# Complete_ePaper_Shoe_Board.net
KiCad netlist of a schematic drawn in EAGLE
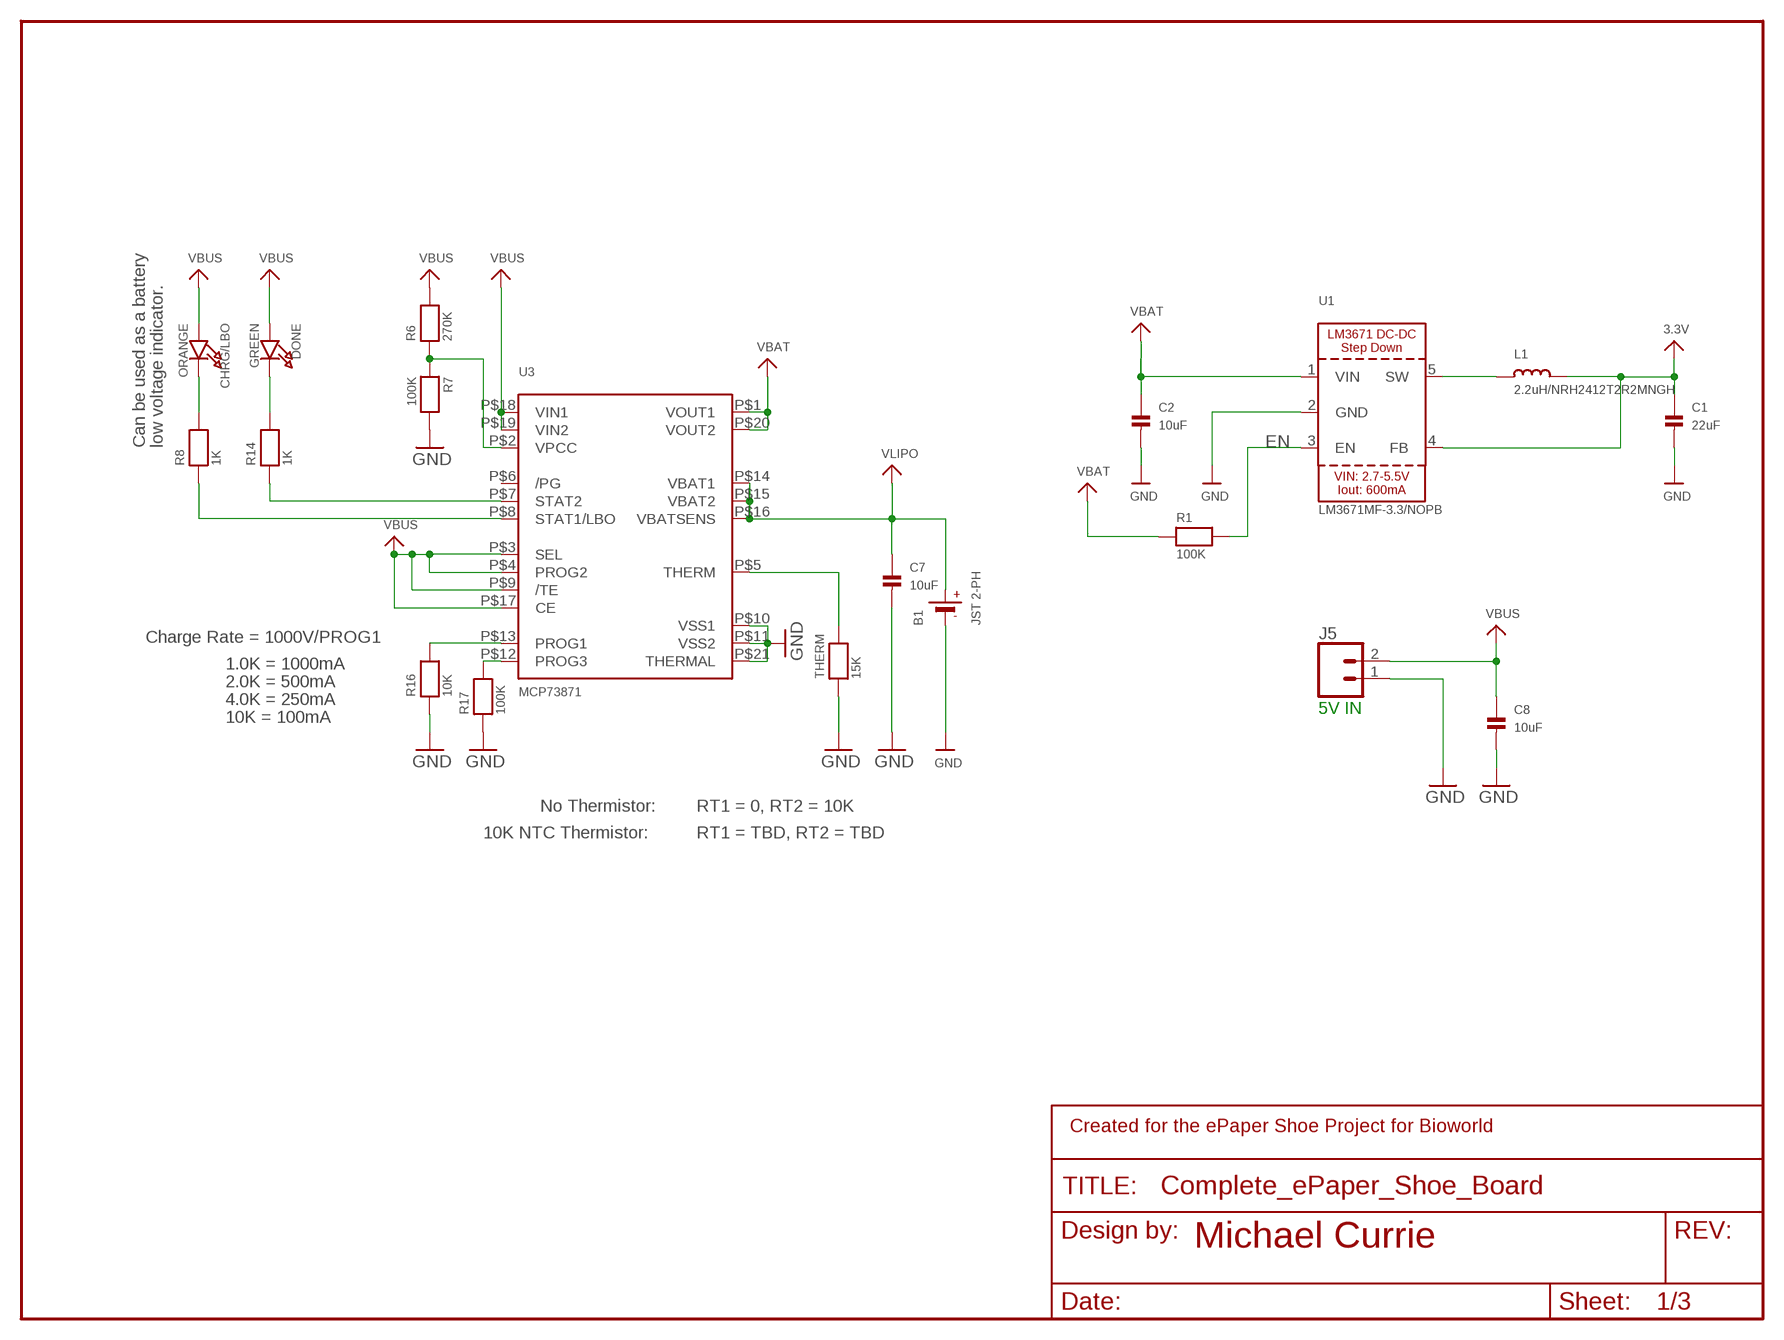
[diagram p0: schematic, sheet 1]
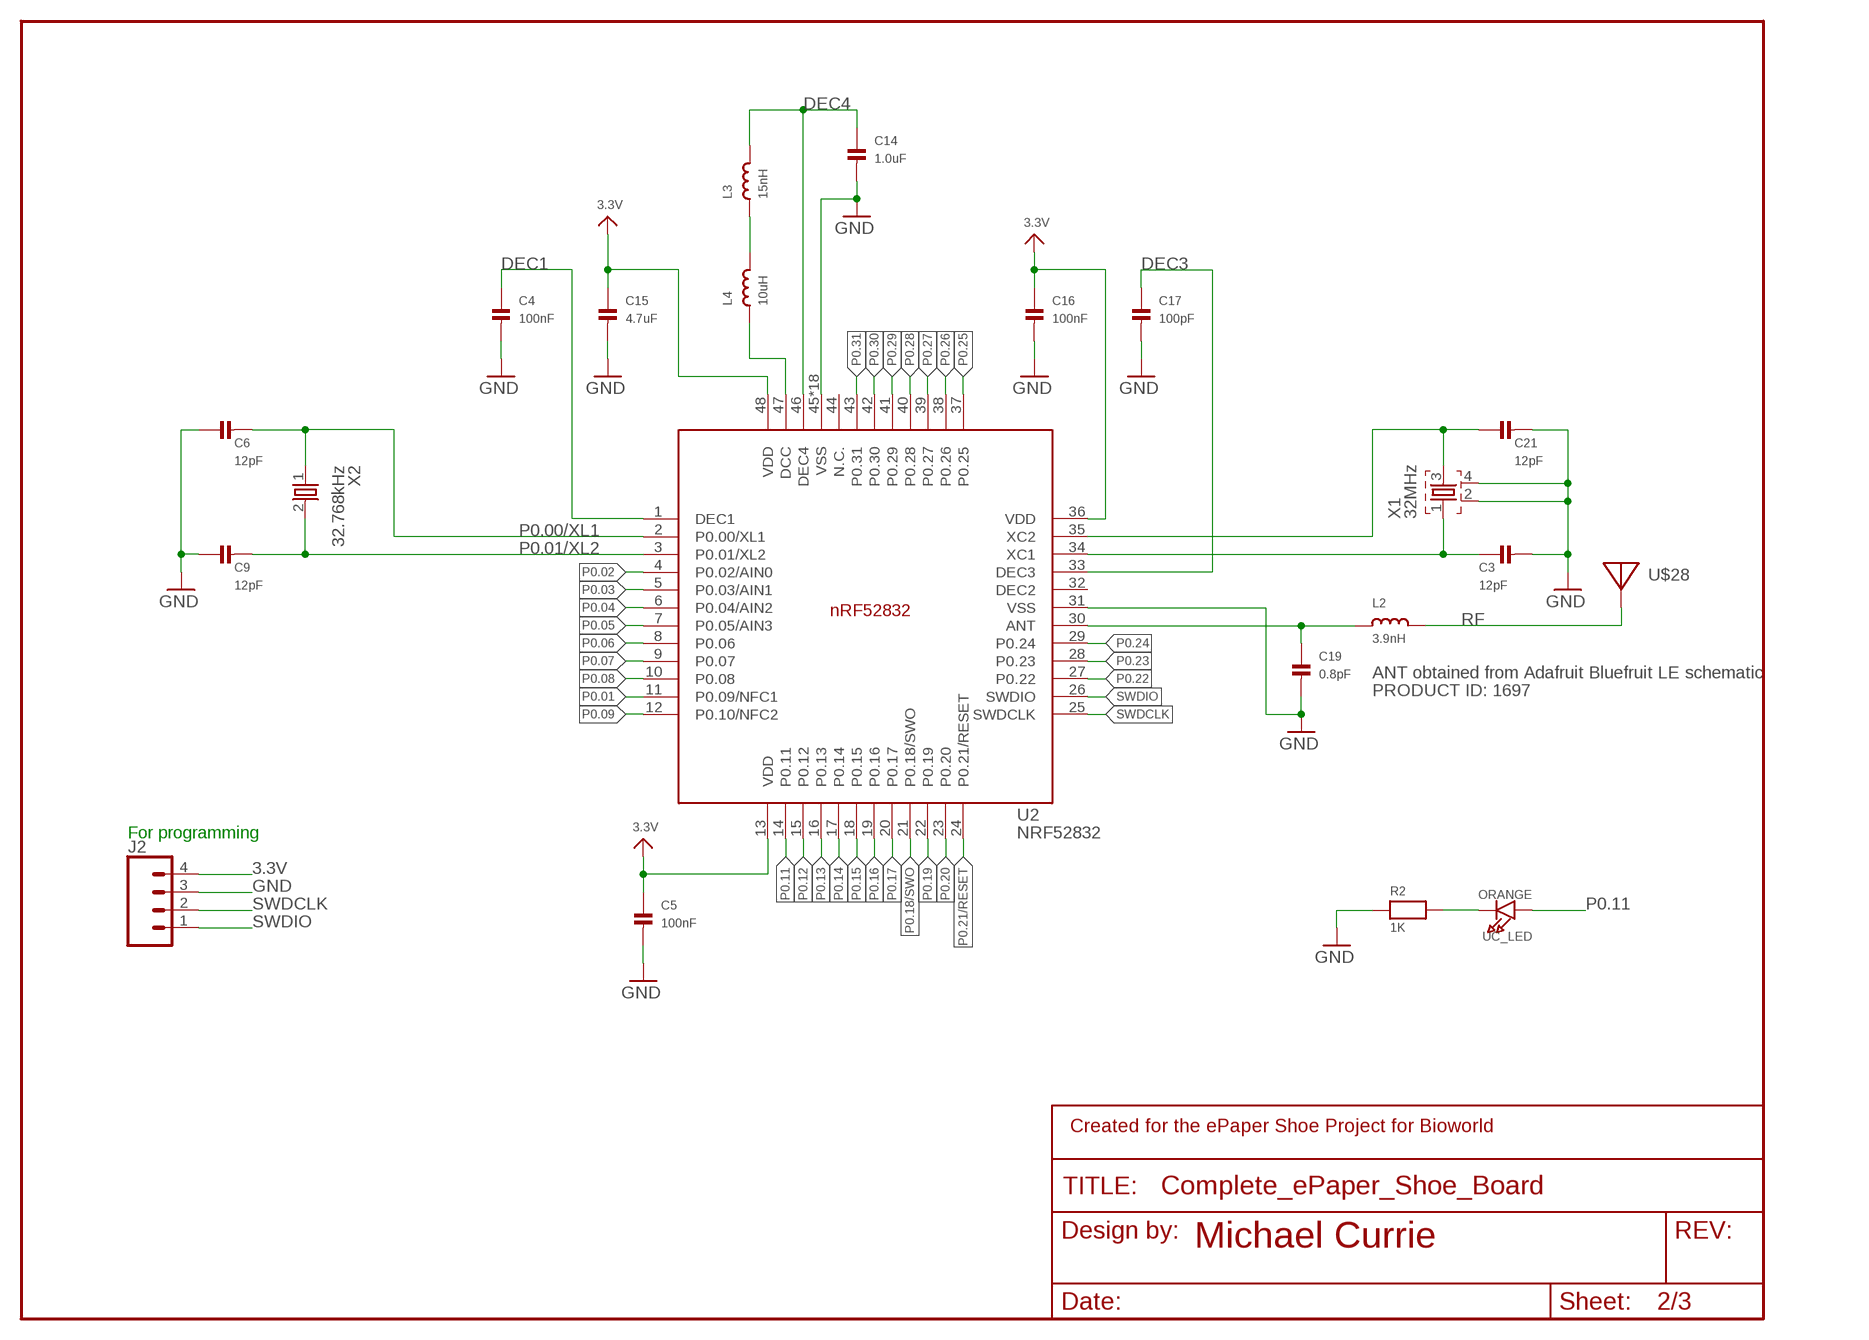
[diagram p1: schematic, sheet 2]
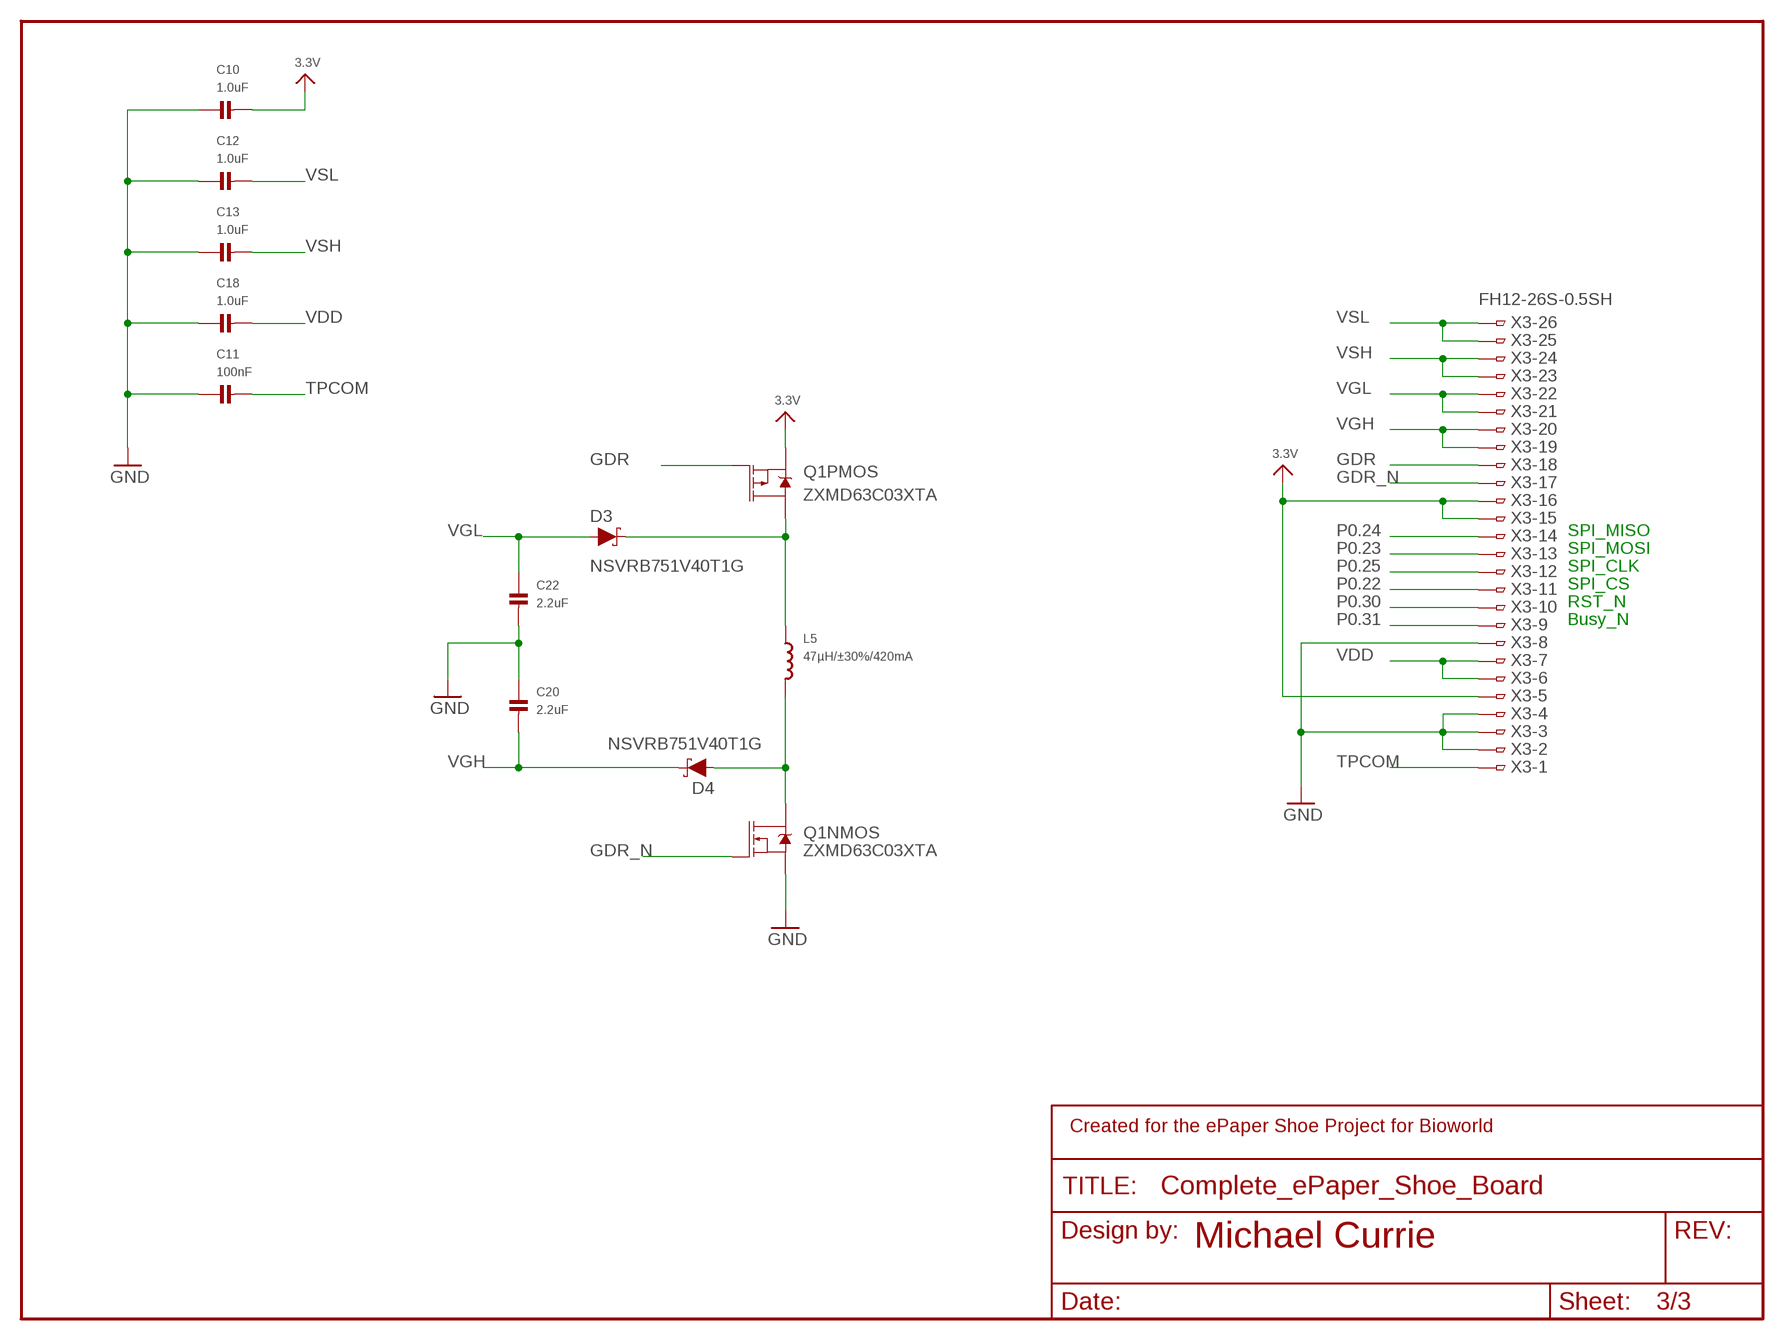
[diagram p2: schematic, sheet 3]

(export (version "E")
  (design (tool "Eeschema 10.0.6"))
  (components
    (comp (ref "C3")
      (value "12pF")
      (footprint "eagle-import:0805")
      (libsource (lib "eagle-import") (part "CAP_CERAMIC0805"))
    )
    (comp (ref "C4")
      (value "100nF")
      (footprint "eagle-import:0805")
      (libsource (lib "eagle-import") (part "CAP_CERAMIC0805"))
    )
    (comp (ref "C5")
      (value "100nF")
      (footprint "eagle-import:0805")
      (libsource (lib "eagle-import") (part "CAP_CERAMIC0805"))
    )
    (comp (ref "C6")
      (value "12pF")
      (footprint "eagle-import:0805")
      (libsource (lib "eagle-import") (part "CAP_CERAMIC0805"))
    )
    (comp (ref "C9")
      (value "12pF")
      (footprint "eagle-import:0805")
      (libsource (lib "eagle-import") (part "CAP_CERAMIC0805"))
    )
    (comp (ref "C14")
      (value "1.0uF")
      (footprint "eagle-import:0805")
      (libsource (lib "eagle-import") (part "CAP_CERAMIC0805"))
    )
    (comp (ref "C15")
      (value "4.7uF")
      (footprint "eagle-import:0805")
      (libsource (lib "eagle-import") (part "CAP_CERAMIC0805"))
    )
    (comp (ref "C16")
      (value "100nF")
      (footprint "eagle-import:0805")
      (libsource (lib "eagle-import") (part "CAP_CERAMIC0805"))
    )
    (comp (ref "C17")
      (value "100pF")
      (footprint "eagle-import:0805")
      (libsource (lib "eagle-import") (part "CAP_CERAMIC0805"))
    )
    (comp (ref "C19")
      (value "0.8pF")
      (footprint "eagle-import:0805")
      (libsource (lib "eagle-import") (part "CAP_CERAMIC0805"))
    )
    (comp (ref "C21")
      (value "12pF")
      (footprint "eagle-import:0805")
      (libsource (lib "eagle-import") (part "CAP_CERAMIC0805"))
    )
    (comp (ref "FRAME2")
      (value "FRAME-LETTER-MICHAELNO_PACKAGE")
      (footprint "eagle-import:DUMMY")
      (fields (field (name "DESIGNER") "Nobody"))
      (libsource (lib "eagle-import") (part "FRAME-LETTER-MICHAELNO_PACKAGE"))
    )
    (comp (ref "J2")
      (value "CONN_04")
      (footprint "eagle-import:1X04")
      (libsource (lib "eagle-import") (part "CONN_04"))
    )
    (comp (ref "L2")
      (value "3.9nH")
      (footprint "eagle-import:0805")
      (libsource (lib "eagle-import") (part "INDUCTOR0805"))
    )
    (comp (ref "L3")
      (value "15nH")
      (footprint "eagle-import:0805")
      (libsource (lib "eagle-import") (part "INDUCTOR0805"))
    )
    (comp (ref "L4")
      (value "10uH")
      (footprint "eagle-import:0805")
      (libsource (lib "eagle-import") (part "INDUCTOR0805"))
    )
    (comp (ref "R2")
      (value "1K")
      (footprint "eagle-import:0805")
      (libsource (lib "eagle-import") (part "RESISTOR0805"))
    )
    (comp (ref "U$28")
      (value "ANTENNA_PCBNRF8001_1.6MM")
      (footprint "eagle-import:ANT_PCB_2.4GHZ_NRF8001_1.6MM_1OZ")
      (libsource (lib "eagle-import") (part "ANTENNA_PCBNRF8001_1.6MM"))
    )
    (comp (ref "U2")
      (value "NRF52832")
      (footprint "eagle-import:QFN40P600X600X90-48_N")
      (libsource (lib "eagle-import") (part "NRF52832"))
    )
    (comp (ref "UC_LED")
      (value "ORANGE")
      (footprint "eagle-import:CHIPLED_0805_NOOUTLINE")
      (libsource (lib "eagle-import") (part "LED0805_NOOUTLINE"))
    )
    (comp (ref "X1")
      (value "32MHz")
      (footprint "eagle-import:BT-XTAL_2016_N")
      (libsource (lib "eagle-import") (part "XTAL_32MHZ"))
    )
    (comp (ref "X2")
      (value "32.768kHz")
      (footprint "eagle-import:XTAL_3215_N")
      (libsource (lib "eagle-import") (part "XTAL_32KHZ"))
    )
    (comp (ref "C10")
      (value "1.0uF")
      (footprint "eagle-import:0805")
      (libsource (lib "eagle-import") (part "CAP_CERAMIC0805"))
    )
    (comp (ref "C11")
      (value "100nF")
      (footprint "eagle-import:0805")
      (libsource (lib "eagle-import") (part "CAP_CERAMIC0805"))
    )
    (comp (ref "C12")
      (value "1.0uF")
      (footprint "eagle-import:0805")
      (libsource (lib "eagle-import") (part "CAP_CERAMIC0805"))
    )
    (comp (ref "C13")
      (value "1.0uF")
      (footprint "eagle-import:0805")
      (libsource (lib "eagle-import") (part "CAP_CERAMIC0805"))
    )
    (comp (ref "C18")
      (value "1.0uF")
      (footprint "eagle-import:0805")
      (libsource (lib "eagle-import") (part "CAP_CERAMIC0805"))
    )
    (comp (ref "C20")
      (value "2.2uF")
      (footprint "eagle-import:0805")
      (libsource (lib "eagle-import") (part "CAP_CERAMIC0805"))
    )
    (comp (ref "C22")
      (value "2.2uF")
      (footprint "eagle-import:0805")
      (libsource (lib "eagle-import") (part "CAP_CERAMIC0805"))
    )
    (comp (ref "D3")
      (value "0.5A/40V/420mV")
      (footprint "eagle-import:SOD-323")
      (libsource (lib "eagle-import") (part "DIODE-SCHOTTKY-PMEG4005EJ"))
    )
    (comp (ref "D4")
      (value "0.5A/40V/420mV")
      (footprint "eagle-import:SOD-323")
      (libsource (lib "eagle-import") (part "DIODE-SCHOTTKY-PMEG4005EJ"))
    )
    (comp (ref "FRAME3")
      (value "FRAME-LETTER-MICHAELNO_PACKAGE")
      (footprint "eagle-import:DUMMY")
      (fields (field (name "DESIGNER") "Nobody"))
      (libsource (lib "eagle-import") (part "FRAME-LETTER-MICHAELNO_PACKAGE"))
    )
    (comp (ref "L5")
      (value "47µH/±30%/420mA")
      (footprint "eagle-import:INDUCTOR_5X5MM_NR5040_NOTHERMALS")
      (libsource (lib "eagle-import") (part "INDUCTORNR5040"))
    )
    (comp (ref "Q1")
      (value "IRF7509")
      (footprint "eagle-import:MSOP8")
      (libsource (lib "eagle-import") (part "IRF7509"))
    )
    (comp (ref "X3")
      (value "FH12-26S-0.5SH")
      (footprint "eagle-import:FH12-26S-0.5SH")
      (fields (field (name "MPN") "FH12-26S-0.5SH(55)"))
      (libsource (lib "eagle-import") (part "FH12-26S-0.5SH"))
    )
    (comp (ref "B1")
      (value "JST 2-PH")
      (footprint "eagle-import:JSTPH2")
      (libsource (lib "eagle-import") (part "BATTERY"))
    )
    (comp (ref "C1")
      (value "22uF")
      (footprint "eagle-import:0805")
      (libsource (lib "eagle-import") (part "CAP_CERAMIC0805"))
    )
    (comp (ref "C2")
      (value "10uF")
      (footprint "eagle-import:0805")
      (libsource (lib "eagle-import") (part "CAP_CERAMIC0805"))
    )
    (comp (ref "C7")
      (value "10uF")
      (footprint "eagle-import:0805")
      (libsource (lib "eagle-import") (part "CAP_CERAMIC0805"))
    )
    (comp (ref "C8")
      (value "10uF")
      (footprint "eagle-import:0805")
      (libsource (lib "eagle-import") (part "CAP_CERAMIC0805"))
    )
    (comp (ref "CHRG/LBO")
      (value "ORANGE")
      (footprint "eagle-import:CHIPLED_0805_NOOUTLINE")
      (libsource (lib "eagle-import") (part "LED0805_NOOUTLINE"))
    )
    (comp (ref "DONE")
      (value "GREEN")
      (footprint "eagle-import:CHIPLED_0805_NOOUTLINE")
      (libsource (lib "eagle-import") (part "LED0805_NOOUTLINE"))
    )
    (comp (ref "FRAME1")
      (value "FRAME-LETTER-MICHAELNO_PACKAGE")
      (footprint "eagle-import:DUMMY")
      (fields (field (name "DESIGNER") "Nobody"))
      (libsource (lib "eagle-import") (part "FRAME-LETTER-MICHAELNO_PACKAGE"))
    )
    (comp (ref "J5")
      (value "CONN_02")
      (footprint "eagle-import:1X02")
      (libsource (lib "eagle-import") (part "CONN_02"))
    )
    (comp (ref "L1")
      (value "2.2uH/NRH2412T2R2MNGH")
      (footprint "eagle-import:INDUCTOR_5X5MM_NR5040_NOTHERMALS")
      (libsource (lib "eagle-import") (part "INDUCTORNR5040"))
    )
    (comp (ref "R1")
      (value "100K")
      (footprint "eagle-import:0805")
      (libsource (lib "eagle-import") (part "RESISTOR0805"))
    )
    (comp (ref "R6")
      (value "270K")
      (footprint "eagle-import:0805")
      (libsource (lib "eagle-import") (part "RESISTOR0805"))
    )
    (comp (ref "R7")
      (value "100K")
      (footprint "eagle-import:0805")
      (libsource (lib "eagle-import") (part "RESISTOR0805"))
    )
    (comp (ref "R8")
      (value "1K")
      (footprint "eagle-import:0805")
      (libsource (lib "eagle-import") (part "RESISTOR0805"))
    )
    (comp (ref "R14")
      (value "1K")
      (footprint "eagle-import:0805")
      (libsource (lib "eagle-import") (part "RESISTOR0805"))
    )
    (comp (ref "R16")
      (value "10K")
      (footprint "eagle-import:0805")
      (libsource (lib "eagle-import") (part "RESISTOR0805"))
    )
    (comp (ref "R17")
      (value "100K")
      (footprint "eagle-import:0805")
      (libsource (lib "eagle-import") (part "RESISTOR0805"))
    )
    (comp (ref "THERM")
      (value "15K")
      (footprint "eagle-import:0805")
      (libsource (lib "eagle-import") (part "RESISTOR0805"))
    )
    (comp (ref "U1")
      (value "LM3671MF-3.3/NOPB")
      (footprint "eagle-import:SOT23-5")
      (libsource (lib "eagle-import") (part "VREG_LM3671"))
    )
    (comp (ref "U3")
      (value "MCP73871")
      (footprint "eagle-import:QFN20_4MM")
      (libsource (lib "eagle-import") (part "MCP73871"))
    )
  )
  (nets
    (net (code "1") (name "3.3V") (class "Default")
      (node (ref "C1") (pin "1") (pinfunction "P$1_1") (pintype "passive"))
      (node (ref "C10") (pin "2") (pinfunction "P$2_2") (pintype "passive"))
      (node (ref "C15") (pin "1") (pinfunction "P$1_1") (pintype "passive"))
      (node (ref "C16") (pin "1") (pinfunction "P$1_1") (pintype "passive"))
      (node (ref "C5") (pin "1") (pinfunction "P$1_1") (pintype "passive"))
      (node (ref "J2") (pin "4") (pinfunction "4_4") (pintype "passive"))
      (node (ref "L1") (pin "P$2") (pinfunction "2_P$2") (pintype "passive"))
      (node (ref "Q1") (pin "3") (pinfunction "S_3") (pintype "bidirectional"))
      (node (ref "U1") (pin "4") (pinfunction "FB_4") (pintype "power_in"))
      (node (ref "U2") (pin "13") (pinfunction "VDD_13") (pintype "power_in"))
      (node (ref "U2") (pin "36") (pinfunction "VDD_36") (pintype "power_in"))
      (node (ref "U2") (pin "48") (pinfunction "VDD_48") (pintype "power_in"))
      (node (ref "X3") (pin "15") (pinfunction "1_15") (pintype "passive"))
      (node (ref "X3") (pin "16") (pinfunction "1_16") (pintype "passive"))
      (node (ref "X3") (pin "5") (pinfunction "1_5") (pintype "passive"))
    )
    (net (code "2") (name "DEC1") (class "Default")
      (node (ref "C4") (pin "1") (pinfunction "P$1_1") (pintype "passive"))
      (node (ref "U2") (pin "1") (pinfunction "DEC1_1") (pintype "power_in"))
    )
    (net (code "3") (name "DEC3") (class "Default")
      (node (ref "C17") (pin "1") (pinfunction "P$1_1") (pintype "passive"))
      (node (ref "U2") (pin "33") (pinfunction "DEC3_33") (pintype "bidirectional"))
    )
    (net (code "4") (name "DEC4") (class "Default")
      (node (ref "C14") (pin "1") (pinfunction "P$1_1") (pintype "passive"))
      (node (ref "L3") (pin "2") (pinfunction "2_2") (pintype "passive"))
      (node (ref "U2") (pin "46") (pinfunction "DEC4_46") (pintype "power_in"))
    )
    (net (code "5") (name "EN") (class "Default")
      (node (ref "R1") (pin "2") (pinfunction "2_2") (pintype "passive"))
      (node (ref "U1") (pin "3") (pinfunction "EN_3") (pintype "input"))
    )
    (net (code "6") (name "GDR") (class "Default")
      (node (ref "Q1") (pin "4") (pinfunction "G_4") (pintype "bidirectional"))
      (node (ref "X3") (pin "18") (pinfunction "1_18") (pintype "passive"))
    )
    (net (code "7") (name "GDR_N") (class "Default")
      (node (ref "Q1") (pin "2") (pinfunction "G_2") (pintype "bidirectional"))
      (node (ref "X3") (pin "17") (pinfunction "1_17") (pintype "passive"))
    )
    (net (code "8") (name "GND") (class "Default")
      (node (ref "B1") (pin "1") (pinfunction "-_1") (pintype "passive"))
      (node (ref "C1") (pin "2") (pinfunction "P$2_2") (pintype "passive"))
      (node (ref "C10") (pin "1") (pinfunction "P$1_1") (pintype "passive"))
      (node (ref "C11") (pin "1") (pinfunction "P$1_1") (pintype "passive"))
      (node (ref "C12") (pin "1") (pinfunction "P$1_1") (pintype "passive"))
      (node (ref "C13") (pin "1") (pinfunction "P$1_1") (pintype "passive"))
      (node (ref "C14") (pin "2") (pinfunction "P$2_2") (pintype "passive"))
      (node (ref "C15") (pin "2") (pinfunction "P$2_2") (pintype "passive"))
      (node (ref "C16") (pin "2") (pinfunction "P$2_2") (pintype "passive"))
      (node (ref "C17") (pin "2") (pinfunction "P$2_2") (pintype "passive"))
      (node (ref "C18") (pin "1") (pinfunction "P$1_1") (pintype "passive"))
      (node (ref "C19") (pin "2") (pinfunction "P$2_2") (pintype "passive"))
      (node (ref "C2") (pin "2") (pinfunction "P$2_2") (pintype "passive"))
      (node (ref "C20") (pin "1") (pinfunction "P$1_1") (pintype "passive"))
      (node (ref "C21") (pin "2") (pinfunction "P$2_2") (pintype "passive"))
      (node (ref "C22") (pin "2") (pinfunction "P$2_2") (pintype "passive"))
      (node (ref "C3") (pin "2") (pinfunction "P$2_2") (pintype "passive"))
      (node (ref "C4") (pin "2") (pinfunction "P$2_2") (pintype "passive"))
      (node (ref "C5") (pin "2") (pinfunction "P$2_2") (pintype "passive"))
      (node (ref "C6") (pin "1") (pinfunction "P$1_1") (pintype "passive"))
      (node (ref "C7") (pin "2") (pinfunction "P$2_2") (pintype "passive"))
      (node (ref "C8") (pin "2") (pinfunction "P$2_2") (pintype "passive"))
      (node (ref "C9") (pin "1") (pinfunction "P$1_1") (pintype "passive"))
      (node (ref "J2") (pin "3") (pinfunction "3_3") (pintype "passive"))
      (node (ref "J5") (pin "1") (pinfunction "1_1") (pintype "passive"))
      (node (ref "Q1") (pin "1") (pinfunction "S_1") (pintype "bidirectional"))
      (node (ref "R16") (pin "1") (pinfunction "1_1") (pintype "passive"))
      (node (ref "R17") (pin "1") (pinfunction "1_1") (pintype "passive"))
      (node (ref "R2") (pin "1") (pinfunction "1_1") (pintype "passive"))
      (node (ref "R7") (pin "2") (pinfunction "2_2") (pintype "passive"))
      (node (ref "THERM") (pin "1") (pinfunction "1_1") (pintype "passive"))
      (node (ref "U1") (pin "2") (pinfunction "GND_2") (pintype "power_in"))
      (node (ref "U2") (pin "31") (pinfunction "VSS_31") (pintype "bidirectional"))
      (node (ref "U2") (pin "45") (pinfunction "VSS_45") (pintype "power_in"))
      (node (ref "U2") (pin "PAD") (pinfunction "VSS_PAD") (pintype "power_in"))
      (node (ref "U2") (pin "PAD@VIA01") (pinfunction "VSS_PAD@VIA01") (pintype "power_in"))
      (node (ref "U2") (pin "PAD@VIA02") (pinfunction "VSS_PAD@VIA02") (pintype "power_in"))
      (node (ref "U2") (pin "PAD@VIA03") (pinfunction "VSS_PAD@VIA03") (pintype "power_in"))
      (node (ref "U2") (pin "PAD@VIA04") (pinfunction "VSS_PAD@VIA04") (pintype "power_in"))
      (node (ref "U2") (pin "PAD@VIA05") (pinfunction "VSS_PAD@VIA05") (pintype "power_in"))
      (node (ref "U2") (pin "PAD@VIA06") (pinfunction "VSS_PAD@VIA06") (pintype "power_in"))
      (node (ref "U2") (pin "PAD@VIA07") (pinfunction "VSS_PAD@VIA07") (pintype "power_in"))
      (node (ref "U2") (pin "PAD@VIA08") (pinfunction "VSS_PAD@VIA08") (pintype "power_in"))
      (node (ref "U2") (pin "PAD@VIA09") (pinfunction "VSS_PAD@VIA09") (pintype "power_in"))
      (node (ref "U2") (pin "PAD@VIA10") (pinfunction "VSS_PAD@VIA10") (pintype "power_in"))
      (node (ref "U2") (pin "PAD@VIA11") (pinfunction "VSS_PAD@VIA11") (pintype "power_in"))
      (node (ref "U2") (pin "PAD@VIA12") (pinfunction "VSS_PAD@VIA12") (pintype "power_in"))
      (node (ref "U2") (pin "PAD@VIA13") (pinfunction "VSS_PAD@VIA13") (pintype "power_in"))
      (node (ref "U2") (pin "PAD@VIA14") (pinfunction "VSS_PAD@VIA14") (pintype "power_in"))
      (node (ref "U2") (pin "PAD@VIA15") (pinfunction "VSS_PAD@VIA15") (pintype "power_in"))
      (node (ref "U2") (pin "PAD@VIA16") (pinfunction "VSS_PAD@VIA16") (pintype "power_in"))
      (node (ref "U3") (pin "P$10") (pinfunction "VSS1_P$10") (pintype "bidirectional"))
      (node (ref "U3") (pin "P$11") (pinfunction "VSS2_P$11") (pintype "bidirectional"))
      (node (ref "U3") (pin "P$21") (pinfunction "THERMAL_P$21") (pintype "bidirectional"))
      (node (ref "X1") (pin "2") (pinfunction "2_2") (pintype "passive"))
      (node (ref "X1") (pin "4") (pinfunction "4_4") (pintype "passive"))
      (node (ref "X3") (pin "2") (pinfunction "1_2") (pintype "passive"))
      (node (ref "X3") (pin "3") (pinfunction "1_3") (pintype "passive"))
      (node (ref "X3") (pin "4") (pinfunction "1_4") (pintype "passive"))
      (node (ref "X3") (pin "8") (pinfunction "1_8") (pintype "passive"))
    )
    (net (code "9") (name "Net-(C3-P$1)") (class "Default")
      (node (ref "C3") (pin "1") (pinfunction "P$1_1") (pintype "passive"))
      (node (ref "U2") (pin "34") (pinfunction "XC1_34") (pintype "input"))
      (node (ref "X1") (pin "1") (pinfunction "1_1") (pintype "passive"))
    )
    (net (code "10") (name "Net-(C19-P$1)") (class "Default")
      (node (ref "C19") (pin "1") (pinfunction "P$1_1") (pintype "passive"))
      (node (ref "L2") (pin "1") (pinfunction "1_1") (pintype "passive"))
      (node (ref "U2") (pin "30") (pinfunction "ANT_30") (pintype "bidirectional"))
    )
    (net (code "11") (name "Net-(C21-P$1)") (class "Default")
      (node (ref "C21") (pin "1") (pinfunction "P$1_1") (pintype "passive"))
      (node (ref "U2") (pin "35") (pinfunction "XC2_35") (pintype "output"))
      (node (ref "X1") (pin "3") (pinfunction "3_3") (pintype "passive"))
    )
    (net (code "12") (name "Net-(CHRG/LBO-PadC)") (class "Default")
      (node (ref "CHRG/LBO") (pin "C") (pinfunction "C_C") (pintype "passive"))
      (node (ref "R8") (pin "2") (pinfunction "2_2") (pintype "passive"))
    )
    (net (code "13") (name "Net-(DONE-PadC)") (class "Default")
      (node (ref "DONE") (pin "C") (pinfunction "C_C") (pintype "passive"))
      (node (ref "R14") (pin "2") (pinfunction "2_2") (pintype "passive"))
    )
    (net (code "14") (name "Net-(L1-1)") (class "Default")
      (node (ref "L1") (pin "P$1") (pinfunction "1_P$1") (pintype "passive"))
      (node (ref "U1") (pin "5") (pinfunction "SW_5") (pintype "output"))
    )
    (net (code "15") (name "Net-(L3-Pad1)") (class "Default")
      (node (ref "L3") (pin "1") (pinfunction "1_1") (pintype "passive"))
      (node (ref "L4") (pin "2") (pinfunction "2_2") (pintype "passive"))
    )
    (net (code "16") (name "Net-(L5-1)") (class "Default")
      (node (ref "D3") (pin "C") (pinfunction "C_C") (pintype "passive"))
      (node (ref "L5") (pin "P$1") (pinfunction "1_P$1") (pintype "passive"))
      (node (ref "Q1") (pin "5") (pinfunction "D_5") (pintype "bidirectional"))
      (node (ref "Q1") (pin "6") (pinfunction "D_6") (pintype "bidirectional"))
    )
    (net (code "17") (name "Net-(L5-2)") (class "Default")
      (node (ref "D4") (pin "A") (pinfunction "A_A") (pintype "passive"))
      (node (ref "L5") (pin "P$2") (pinfunction "2_P$2") (pintype "passive"))
      (node (ref "Q1") (pin "7") (pinfunction "D_7") (pintype "bidirectional"))
      (node (ref "Q1") (pin "8") (pinfunction "D_8") (pintype "bidirectional"))
    )
    (net (code "18") (name "Net-(R2-Pad2)") (class "Default")
      (node (ref "R2") (pin "2") (pinfunction "2_2") (pintype "passive"))
      (node (ref "UC_LED") (pin "C") (pinfunction "C_C") (pintype "passive"))
    )
    (net (code "19") (name "Net-(U2-DCC)") (class "Default")
      (node (ref "L4") (pin "1") (pinfunction "1_1") (pintype "passive"))
      (node (ref "U2") (pin "47") (pinfunction "DCC_47") (pintype "output"))
    )
    (net (code "20") (name "Net-(U3-PROG1)") (class "Default")
      (node (ref "R16") (pin "2") (pinfunction "2_2") (pintype "passive"))
      (node (ref "U3") (pin "P$13") (pinfunction "PROG1_P$13") (pintype "bidirectional"))
    )
    (net (code "21") (name "Net-(U3-PROG3)") (class "Default")
      (node (ref "R17") (pin "2") (pinfunction "2_2") (pintype "passive"))
      (node (ref "U3") (pin "P$12") (pinfunction "PROG3_P$12") (pintype "bidirectional"))
    )
    (net (code "22") (name "Net-(U3-STAT1{slash}LBO)") (class "Default")
      (node (ref "R8") (pin "1") (pinfunction "1_1") (pintype "passive"))
      (node (ref "U3") (pin "P$8") (pinfunction "STAT1/LBO_P$8") (pintype "bidirectional"))
    )
    (net (code "23") (name "Net-(U3-STAT2)") (class "Default")
      (node (ref "R14") (pin "1") (pinfunction "1_1") (pintype "passive"))
      (node (ref "U3") (pin "P$7") (pinfunction "STAT2_P$7") (pintype "bidirectional"))
    )
    (net (code "24") (name "Net-(U3-THERM)") (class "Default")
      (node (ref "THERM") (pin "2") (pinfunction "2_2") (pintype "passive"))
      (node (ref "U3") (pin "P$5") (pinfunction "THERM_P$5") (pintype "bidirectional"))
    )
    (net (code "25") (name "Net-(U3-VPCC)") (class "Default")
      (node (ref "R6") (pin "1") (pinfunction "1_1") (pintype "passive"))
      (node (ref "R7") (pin "1") (pinfunction "1_1") (pintype "passive"))
      (node (ref "U3") (pin "P$2") (pinfunction "VPCC_P$2") (pintype "bidirectional"))
    )
    (net (code "26") (name "P0.00{slash}XL1") (class "Default")
      (node (ref "C6") (pin "2") (pinfunction "P$2_2") (pintype "passive"))
      (node (ref "U2") (pin "2") (pinfunction "P0.00/XL1_2") (pintype "bidirectional"))
      (node (ref "X2") (pin "1") (pinfunction "1_1") (pintype "passive"))
    )
    (net (code "27") (name "P0.01") (class "Default")
      (node (ref "U2") (pin "11") (pinfunction "P0.09/NFC1_11") (pintype "bidirectional"))
    )
    (net (code "28") (name "P0.01{slash}XL2") (class "Default")
      (node (ref "C9") (pin "2") (pinfunction "P$2_2") (pintype "passive"))
      (node (ref "U2") (pin "3") (pinfunction "P0.01/XL2_3") (pintype "bidirectional"))
      (node (ref "X2") (pin "2") (pinfunction "2_2") (pintype "passive"))
    )
    (net (code "29") (name "P0.02") (class "Default")
      (node (ref "U2") (pin "4") (pinfunction "P0.02/AIN0_4") (pintype "bidirectional"))
    )
    (net (code "30") (name "P0.03") (class "Default")
      (node (ref "U2") (pin "5") (pinfunction "P0.03/AIN1_5") (pintype "bidirectional"))
    )
    (net (code "31") (name "P0.04") (class "Default")
      (node (ref "U2") (pin "6") (pinfunction "P0.04/AIN2_6") (pintype "bidirectional"))
    )
    (net (code "32") (name "P0.05") (class "Default")
      (node (ref "U2") (pin "7") (pinfunction "P0.05/AIN3_7") (pintype "bidirectional"))
    )
    (net (code "33") (name "P0.06") (class "Default")
      (node (ref "U2") (pin "8") (pinfunction "P0.06_8") (pintype "bidirectional"))
    )
    (net (code "34") (name "P0.07") (class "Default")
      (node (ref "U2") (pin "9") (pinfunction "P0.07_9") (pintype "bidirectional"))
    )
    (net (code "35") (name "P0.08") (class "Default")
      (node (ref "U2") (pin "10") (pinfunction "P0.08_10") (pintype "bidirectional"))
    )
    (net (code "36") (name "P0.09") (class "Default")
      (node (ref "U2") (pin "12") (pinfunction "P0.10/NFC2_12") (pintype "bidirectional"))
    )
    (net (code "37") (name "P0.11") (class "Default")
      (node (ref "U2") (pin "14") (pinfunction "P0.11_14") (pintype "bidirectional"))
      (node (ref "UC_LED") (pin "A") (pinfunction "A_A") (pintype "passive"))
    )
    (net (code "38") (name "P0.12") (class "Default")
      (node (ref "U2") (pin "15") (pinfunction "P0.12_15") (pintype "bidirectional"))
    )
    (net (code "39") (name "P0.13") (class "Default")
      (node (ref "U2") (pin "16") (pinfunction "P0.13_16") (pintype "bidirectional"))
    )
    (net (code "40") (name "P0.14") (class "Default")
      (node (ref "U2") (pin "17") (pinfunction "P0.14_17") (pintype "bidirectional"))
    )
    (net (code "41") (name "P0.15") (class "Default")
      (node (ref "U2") (pin "18") (pinfunction "P0.15_18") (pintype "bidirectional"))
    )
    (net (code "42") (name "P0.16") (class "Default")
      (node (ref "U2") (pin "19") (pinfunction "P0.16_19") (pintype "bidirectional"))
    )
    (net (code "43") (name "P0.17") (class "Default")
      (node (ref "U2") (pin "20") (pinfunction "P0.17_20") (pintype "bidirectional"))
    )
    (net (code "44") (name "P0.18{slash}SWO") (class "Default")
      (node (ref "U2") (pin "21") (pinfunction "P0.18/SWO_21") (pintype "bidirectional"))
    )
    (net (code "45") (name "P0.19") (class "Default")
      (node (ref "U2") (pin "22") (pinfunction "P0.19_22") (pintype "bidirectional"))
    )
    (net (code "46") (name "P0.20") (class "Default")
      (node (ref "U2") (pin "23") (pinfunction "P0.20_23") (pintype "bidirectional"))
    )
    (net (code "47") (name "P0.21{slash}RESET") (class "Default")
      (node (ref "U2") (pin "24") (pinfunction "P0.21/RESET_24") (pintype "bidirectional"))
    )
    (net (code "48") (name "P0.22") (class "Default")
      (node (ref "U2") (pin "27") (pinfunction "P0.22_27") (pintype "bidirectional"))
      (node (ref "X3") (pin "11") (pinfunction "1_11") (pintype "passive"))
    )
    (net (code "49") (name "P0.23") (class "Default")
      (node (ref "U2") (pin "28") (pinfunction "P0.23_28") (pintype "bidirectional"))
      (node (ref "X3") (pin "13") (pinfunction "1_13") (pintype "passive"))
    )
    (net (code "50") (name "P0.24") (class "Default")
      (node (ref "U2") (pin "29") (pinfunction "P0.24_29") (pintype "bidirectional"))
      (node (ref "X3") (pin "14") (pinfunction "1_14") (pintype "passive"))
    )
    (net (code "51") (name "P0.25") (class "Default")
      (node (ref "U2") (pin "37") (pinfunction "P0.25_37") (pintype "bidirectional"))
      (node (ref "X3") (pin "12") (pinfunction "1_12") (pintype "passive"))
    )
    (net (code "52") (name "P0.26") (class "Default")
      (node (ref "U2") (pin "38") (pinfunction "P0.26_38") (pintype "bidirectional"))
    )
    (net (code "53") (name "P0.27") (class "Default")
      (node (ref "U2") (pin "39") (pinfunction "P0.27_39") (pintype "bidirectional"))
    )
    (net (code "54") (name "P0.28") (class "Default")
      (node (ref "U2") (pin "40") (pinfunction "P0.28_40") (pintype "bidirectional"))
    )
    (net (code "55") (name "P0.29") (class "Default")
      (node (ref "U2") (pin "41") (pinfunction "P0.29_41") (pintype "bidirectional"))
    )
    (net (code "56") (name "P0.30") (class "Default")
      (node (ref "U2") (pin "42") (pinfunction "P0.30_42") (pintype "bidirectional"))
      (node (ref "X3") (pin "10") (pinfunction "1_10") (pintype "passive"))
    )
    (net (code "57") (name "P0.31") (class "Default")
      (node (ref "U2") (pin "43") (pinfunction "P0.31_43") (pintype "bidirectional"))
      (node (ref "X3") (pin "9") (pinfunction "1_9") (pintype "passive"))
    )
    (net (code "58") (name "RF") (class "Default")
      (node (ref "L2") (pin "2") (pinfunction "2_2") (pintype "passive"))
      (node (ref "U$28") (pin "FEED") (pinfunction "P$1_FEED") (pintype "passive"))
    )
    (net (code "59") (name "SWDCLK") (class "Default")
      (node (ref "J2") (pin "2") (pinfunction "2_2") (pintype "passive"))
      (node (ref "U2") (pin "25") (pinfunction "SWDCLK_25") (pintype "input"))
    )
    (net (code "60") (name "SWDIO") (class "Default")
      (node (ref "J2") (pin "1") (pinfunction "1_1") (pintype "passive"))
      (node (ref "U2") (pin "26") (pinfunction "SWDIO_26") (pintype "bidirectional"))
    )
    (net (code "61") (name "TPCOM") (class "Default")
      (node (ref "C11") (pin "2") (pinfunction "P$2_2") (pintype "passive"))
      (node (ref "X3") (pin "1") (pinfunction "1_1") (pintype "passive"))
    )
    (net (code "62") (name "VBAT") (class "Default")
      (node (ref "C2") (pin "1") (pinfunction "P$1_1") (pintype "passive"))
      (node (ref "R1") (pin "1") (pinfunction "1_1") (pintype "passive"))
      (node (ref "U1") (pin "1") (pinfunction "VIN_1") (pintype "power_in"))
      (node (ref "U3") (pin "P$1") (pinfunction "VOUT1_P$1") (pintype "bidirectional"))
      (node (ref "U3") (pin "P$20") (pinfunction "VOUT2_P$20") (pintype "bidirectional"))
    )
    (net (code "63") (name "VBUS") (class "Default")
      (node (ref "C8") (pin "1") (pinfunction "P$1_1") (pintype "passive"))
      (node (ref "CHRG/LBO") (pin "A") (pinfunction "A_A") (pintype "passive"))
      (node (ref "DONE") (pin "A") (pinfunction "A_A") (pintype "passive"))
      (node (ref "J5") (pin "2") (pinfunction "2_2") (pintype "passive"))
      (node (ref "R6") (pin "2") (pinfunction "2_2") (pintype "passive"))
      (node (ref "U3") (pin "P$17") (pinfunction "CE_P$17") (pintype "bidirectional"))
      (node (ref "U3") (pin "P$18") (pinfunction "VIN1_P$18") (pintype "bidirectional"))
      (node (ref "U3") (pin "P$19") (pinfunction "VIN2_P$19") (pintype "bidirectional"))
      (node (ref "U3") (pin "P$3") (pinfunction "SEL_P$3") (pintype "bidirectional"))
      (node (ref "U3") (pin "P$4") (pinfunction "PROG2_P$4") (pintype "bidirectional"))
      (node (ref "U3") (pin "P$9") (pinfunction "/TE_P$9") (pintype "bidirectional"))
    )
    (net (code "64") (name "VDD") (class "Default")
      (node (ref "C18") (pin "2") (pinfunction "P$2_2") (pintype "passive"))
      (node (ref "X3") (pin "6") (pinfunction "1_6") (pintype "passive"))
      (node (ref "X3") (pin "7") (pinfunction "1_7") (pintype "passive"))
    )
    (net (code "65") (name "VGH") (class "Default")
      (node (ref "C20") (pin "2") (pinfunction "P$2_2") (pintype "passive"))
      (node (ref "D4") (pin "C") (pinfunction "C_C") (pintype "passive"))
      (node (ref "X3") (pin "19") (pinfunction "1_19") (pintype "passive"))
      (node (ref "X3") (pin "20") (pinfunction "1_20") (pintype "passive"))
    )
    (net (code "66") (name "VGL") (class "Default")
      (node (ref "C22") (pin "1") (pinfunction "P$1_1") (pintype "passive"))
      (node (ref "D3") (pin "A") (pinfunction "A_A") (pintype "passive"))
      (node (ref "X3") (pin "21") (pinfunction "1_21") (pintype "passive"))
      (node (ref "X3") (pin "22") (pinfunction "1_22") (pintype "passive"))
    )
    (net (code "67") (name "VLIPO") (class "Default")
      (node (ref "B1") (pin "2") (pinfunction "+_2") (pintype "passive"))
      (node (ref "C7") (pin "1") (pinfunction "P$1_1") (pintype "passive"))
      (node (ref "U3") (pin "P$14") (pinfunction "VBAT1_P$14") (pintype "bidirectional"))
      (node (ref "U3") (pin "P$15") (pinfunction "VBAT2_P$15") (pintype "bidirectional"))
      (node (ref "U3") (pin "P$16") (pinfunction "VBATSENS_P$16") (pintype "bidirectional"))
    )
    (net (code "68") (name "VSH") (class "Default")
      (node (ref "C13") (pin "2") (pinfunction "P$2_2") (pintype "passive"))
      (node (ref "X3") (pin "23") (pinfunction "1_23") (pintype "passive"))
      (node (ref "X3") (pin "24") (pinfunction "1_24") (pintype "passive"))
    )
    (net (code "69") (name "VSL") (class "Default")
      (node (ref "C12") (pin "2") (pinfunction "P$2_2") (pintype "passive"))
      (node (ref "X3") (pin "25") (pinfunction "1_25") (pintype "passive"))
      (node (ref "X3") (pin "26") (pinfunction "1_26") (pintype "passive"))
    )
    (net (code "70") (name "unconnected-(U2-DEC2-Pad32)") (class "Default")
      (node (ref "U2") (pin "32") (pinfunction "DEC2_32") (pintype "bidirectional"))
    )
    (net (code "71") (name "unconnected-(U2-N.C.-Pad44)") (class "Default")
      (node (ref "U2") (pin "44") (pinfunction "N.C._44") (pintype "no_connect"))
    )
    (net (code "72") (name "unconnected-(U3-{slash}PG-PadP$6)") (class "Default")
      (node (ref "U3") (pin "P$6") (pinfunction "/PG_P$6") (pintype "bidirectional"))
    )
  )
)
